# StartingPoint.net
KiCad netlist of a schematic drawn in EAGLE
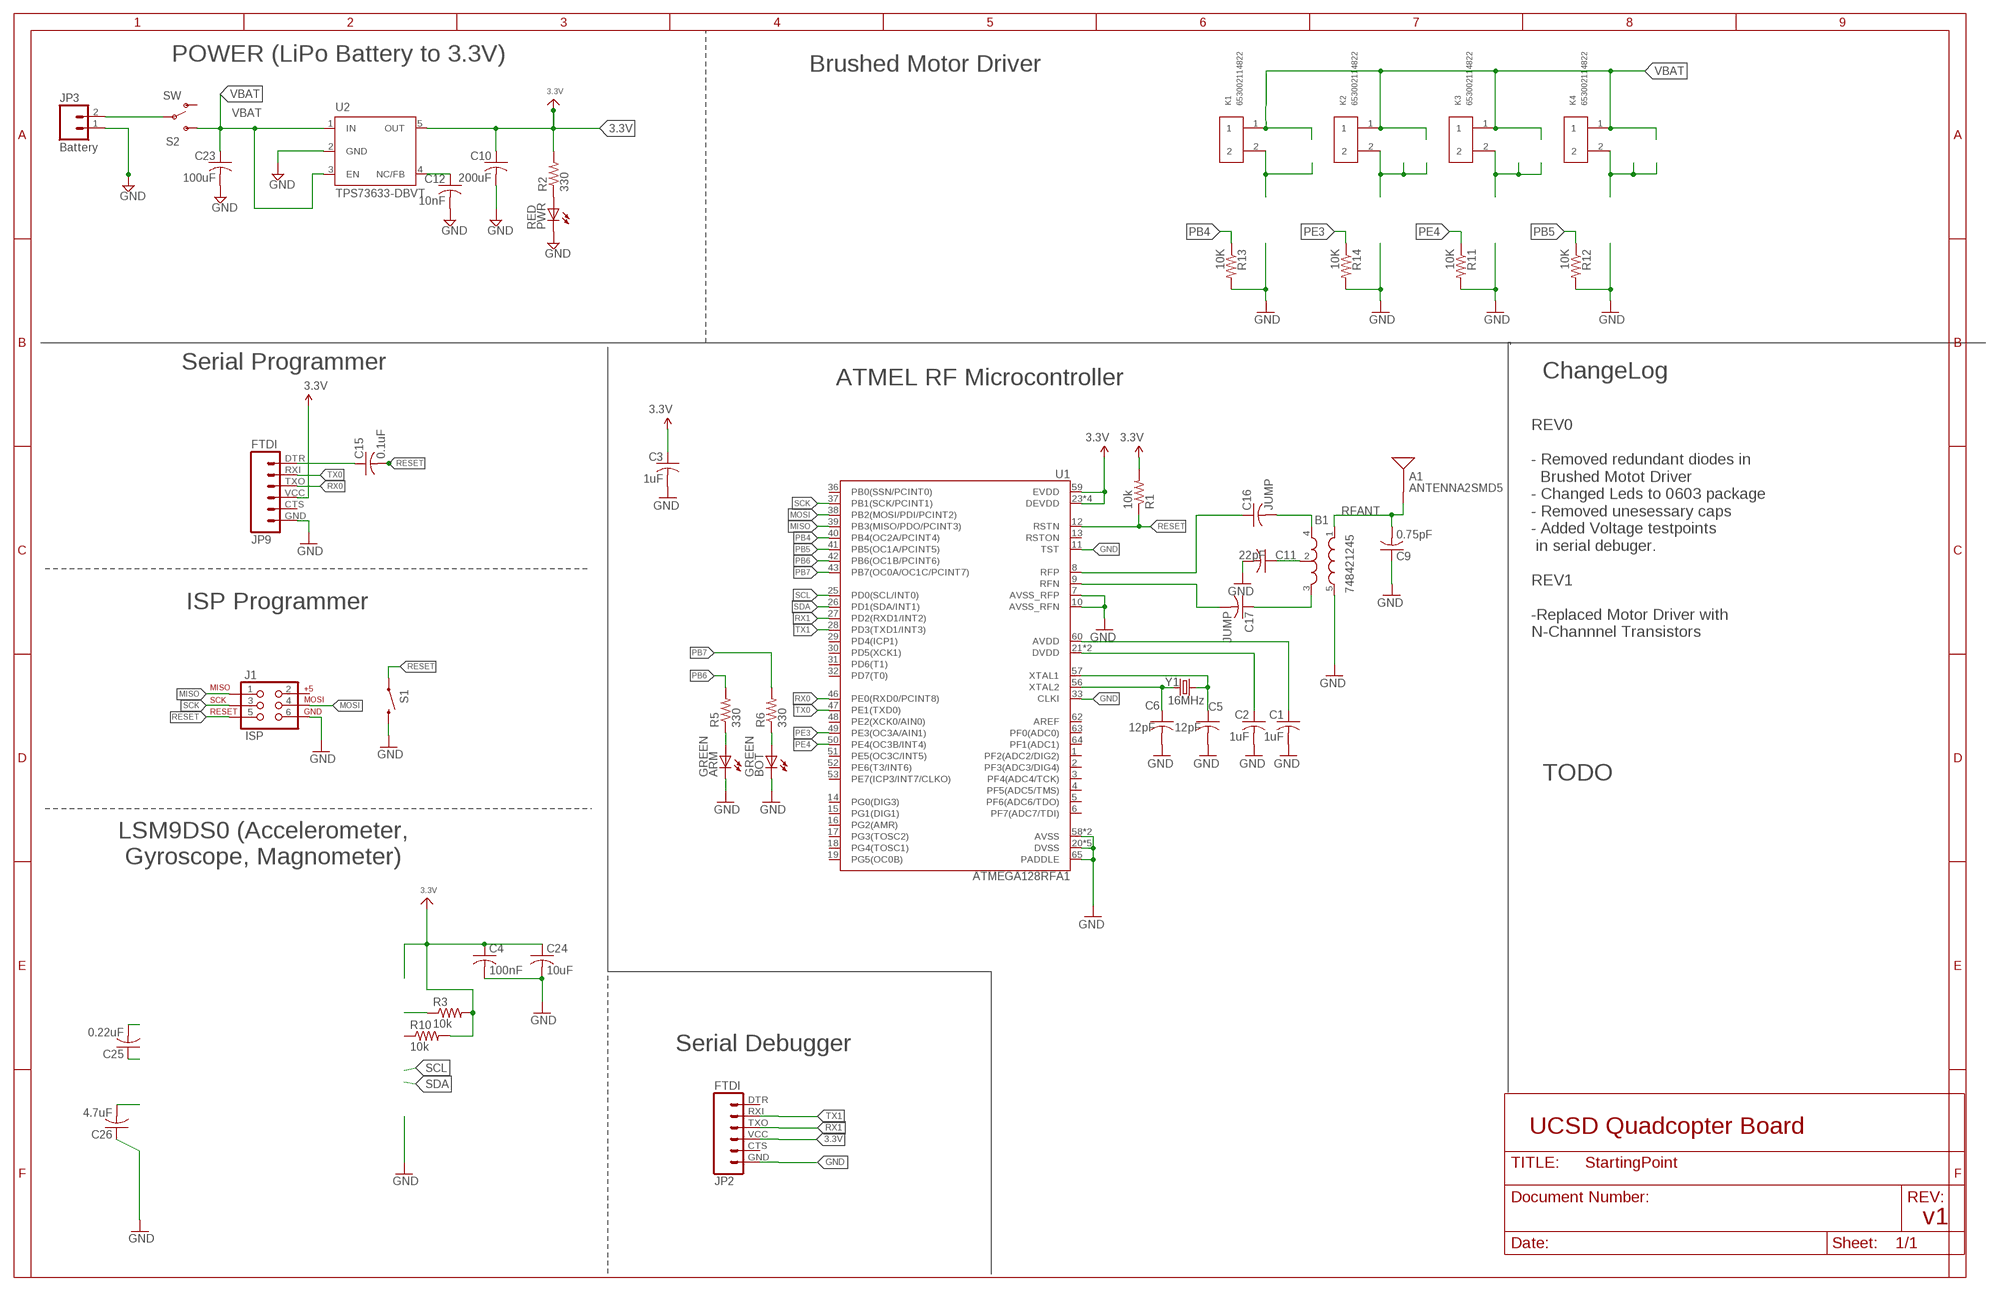
[diagram p0: schematic, sheet 1]

(export (version "E")
  (design (tool "Eeschema 10.0.6"))
  (components
    (comp (ref "A1")
      (value "ANTENNA2SMD5")
      (footprint "eagle-import:ANTENNA-CHIP5")
      (libsource (lib "eagle-import") (part "ANTENNA2SMD5"))
    )
    (comp (ref "ARM")
      (value "GREEN")
      (footprint "eagle-import:CHIP-LED0805")
      (libsource (lib "eagle-import") (part "LEDCHIP-LED0805"))
    )
    (comp (ref "B1")
      (value "748421245")
      (footprint "eagle-import:BALUN")
      (libsource (lib "eagle-import") (part "BALUN0805"))
    )
    (comp (ref "BOT")
      (value "GREEN")
      (footprint "eagle-import:CHIP-LED0805")
      (libsource (lib "eagle-import") (part "LEDCHIP-LED0805"))
    )
    (comp (ref "C1")
      (value "1uF")
      (footprint "eagle-import:C0805")
      (libsource (lib "eagle-import") (part "resistor_C-USC0805"))
    )
    (comp (ref "C2")
      (value "1uF")
      (footprint "eagle-import:C0805")
      (libsource (lib "eagle-import") (part "resistor_C-USC0805"))
    )
    (comp (ref "C3")
      (value "1uF")
      (footprint "eagle-import:C0805")
      (libsource (lib "eagle-import") (part "resistor_C-USC0805"))
    )
    (comp (ref "C4")
      (value "100nF")
      (footprint "eagle-import:C0805")
      (libsource (lib "eagle-import") (part "C-USC0805"))
    )
    (comp (ref "C5")
      (value "12pF")
      (footprint "eagle-import:C0805")
      (libsource (lib "eagle-import") (part "resistor_C-USC0805"))
    )
    (comp (ref "C6")
      (value "12pF")
      (footprint "eagle-import:C0805")
      (libsource (lib "eagle-import") (part "resistor_C-USC0805"))
    )
    (comp (ref "C9")
      (value "0.75pF")
      (footprint "eagle-import:C0805")
      (libsource (lib "eagle-import") (part "resistor_C-USC0805"))
    )
    (comp (ref "C10")
      (value "200uF")
      (footprint "eagle-import:C0805")
      (libsource (lib "eagle-import") (part "resistor_C-USC0805"))
    )
    (comp (ref "C11")
      (value "22pF")
      (footprint "eagle-import:C0805")
      (libsource (lib "eagle-import") (part "resistor_C-USC0805"))
    )
    (comp (ref "C12")
      (value "10nF")
      (footprint "eagle-import:C0805")
      (libsource (lib "eagle-import") (part "resistor_C-USC0805"))
    )
    (comp (ref "C15")
      (value "0.1uF")
      (footprint "eagle-import:C0805")
      (libsource (lib "eagle-import") (part "resistor_C-USC0805"))
    )
    (comp (ref "C16")
      (value "JUMP")
      (footprint "eagle-import:C0805")
      (libsource (lib "eagle-import") (part "resistor_C-USC0805"))
    )
    (comp (ref "C17")
      (value "JUMP")
      (footprint "eagle-import:C0805")
      (libsource (lib "eagle-import") (part "resistor_C-USC0805"))
    )
    (comp (ref "C23")
      (value "100uF")
      (footprint "eagle-import:C0805")
      (libsource (lib "eagle-import") (part "resistor_C-USC0805"))
    )
    (comp (ref "C24")
      (value "10uF")
      (footprint "eagle-import:C0805")
      (libsource (lib "eagle-import") (part "C-USC0805"))
    )
    (comp (ref "C25")
      (value "0.22uF")
      (footprint "eagle-import:C0805")
      (libsource (lib "eagle-import") (part "C-USC0805"))
    )
    (comp (ref "C26")
      (value "4.7uF")
      (footprint "eagle-import:C0805")
      (libsource (lib "eagle-import") (part "C-USC0805"))
    )
    (comp (ref "J1")
      (value "ISP")
      (footprint "eagle-import:2X3-NS")
      (libsource (lib "eagle-import") (part "AVR_SPI_PRG_6NS"))
    )
    (comp (ref "JP2")
      (value "FTDI")
      (footprint "eagle-import:FTDI_BASIC")
      (libsource (lib "eagle-import") (part "FTDI_BASICPTH"))
    )
    (comp (ref "JP3")
      (value "Battery")
      (footprint "eagle-import:1X02")
      (libsource (lib "eagle-import") (part "M02PTH"))
    )
    (comp (ref "JP9")
      (value "FTDI")
      (footprint "eagle-import:FTDI_BASIC")
      (libsource (lib "eagle-import") (part "FTDI_BASICPTH"))
    )
    (comp (ref "K1")
      (value "653002114822")
      (footprint "eagle-import:653002114822")
      (libsource (lib "eagle-import") (part "653002114822"))
    )
    (comp (ref "K2")
      (value "653002114822")
      (footprint "eagle-import:653002114822")
      (libsource (lib "eagle-import") (part "653002114822"))
    )
    (comp (ref "K3")
      (value "653002114822")
      (footprint "eagle-import:653002114822")
      (libsource (lib "eagle-import") (part "653002114822"))
    )
    (comp (ref "K4")
      (value "653002114822")
      (footprint "eagle-import:653002114822")
      (libsource (lib "eagle-import") (part "653002114822"))
    )
    (comp (ref "PWR")
      (value "RED")
      (footprint "eagle-import:CHIP-LED0805")
      (libsource (lib "eagle-import") (part "LEDCHIP-LED0805"))
    )
    (comp (ref "R1")
      (value "10k")
      (footprint "eagle-import:R0805")
      (libsource (lib "eagle-import") (part "R-US_R0805"))
    )
    (comp (ref "R2")
      (value "330")
      (footprint "eagle-import:R0805")
      (libsource (lib "eagle-import") (part "R-US_R0805"))
    )
    (comp (ref "R3")
      (value "10k")
      (footprint "eagle-import:R0805")
      (libsource (lib "eagle-import") (part "R-US_R0805"))
    )
    (comp (ref "R5")
      (value "330")
      (footprint "eagle-import:R0805")
      (libsource (lib "eagle-import") (part "R-US_R0805"))
    )
    (comp (ref "R6")
      (value "330")
      (footprint "eagle-import:R0805")
      (libsource (lib "eagle-import") (part "R-US_R0805"))
    )
    (comp (ref "R10")
      (value "10k")
      (footprint "eagle-import:R0805")
      (libsource (lib "eagle-import") (part "R-US_R0805"))
    )
    (comp (ref "R11")
      (value "10K")
      (footprint "eagle-import:R0805")
      (libsource (lib "eagle-import") (part "R-US_R0805"))
    )
    (comp (ref "R12")
      (value "10K")
      (footprint "eagle-import:R0805")
      (libsource (lib "eagle-import") (part "R-US_R0805"))
    )
    (comp (ref "R13")
      (value "10K")
      (footprint "eagle-import:R0805")
      (libsource (lib "eagle-import") (part "R-US_R0805"))
    )
    (comp (ref "R14")
      (value "10K")
      (footprint "eagle-import:R0805")
      (libsource (lib "eagle-import") (part "R-US_R0805"))
    )
    (comp (ref "S1")
      (value "SWITCH-MOMENTARY-2SMD")
      (footprint "eagle-import:TACTILE_SWITCH_SMD")
      (libsource (lib "eagle-import") (part "SWITCH-MOMENTARY-2SMD"))
    )
    (comp (ref "S2")
      (value "SW")
      (footprint "eagle-import:SWITCH-SPDT")
      (libsource (lib "eagle-import") (part "SWITCH-SPDTPTH"))
    )
    (comp (ref "U1")
      (value "ATMEGA128RFA1")
      (footprint "eagle-import:QFN-64")
      (libsource (lib "eagle-import") (part "ATMEGA128RFA1"))
    )
    (comp (ref "U2")
      (value "TPS73633-DBVT")
      (footprint "eagle-import:SOT23-DBV")
      (libsource (lib "eagle-import") (part "TPS73633-DBVT"))
    )
    (comp (ref "Y1")
      (value "16MHz")
      (footprint "eagle-import:CRYSTAL-SMD-5X3")
      (libsource (lib "eagle-import") (part "CRYSTAL5X3"))
    )
  )
  (nets
    (net (code "1") (name "/RFANT") (class "Default")
      (node (ref "A1") (pin "FEED") (pinfunction "SIGNAL_FEED") (pintype "bidirectional"))
      (node (ref "B1") (pin "1") (pinfunction "IN_1") (pintype "bidirectional"))
      (node (ref "C9") (pin "2") (pinfunction "2_2") (pintype "passive"))
    )
    (net (code "2") (name "3.3V") (class "Default")
      (node (ref "C10") (pin "1") (pinfunction "1_1") (pintype "passive"))
      (node (ref "C24") (pin "1") (pinfunction "1_1") (pintype "passive"))
      (node (ref "C3") (pin "1") (pinfunction "1_1") (pintype "passive"))
      (node (ref "C4") (pin "1") (pinfunction "1_1") (pintype "passive"))
      (node (ref "JP2") (pin "VCC") (pinfunction "4_VCC") (pintype "passive"))
      (node (ref "JP9") (pin "VCC") (pinfunction "4_VCC") (pintype "passive"))
      (node (ref "R1") (pin "2") (pinfunction "2_2") (pintype "passive"))
      (node (ref "R10") (pin "2") (pinfunction "2_2") (pintype "passive"))
      (node (ref "R2") (pin "2") (pinfunction "2_2") (pintype "passive"))
      (node (ref "R3") (pin "2") (pinfunction "2_2") (pintype "passive"))
      (node (ref "U1") (pin "23") (pinfunction "DEVDD_23") (pintype "bidirectional"))
      (node (ref "U1") (pin "34") (pinfunction "DEVDD_34") (pintype "bidirectional"))
      (node (ref "U1") (pin "44") (pinfunction "DEVDD_44") (pintype "bidirectional"))
      (node (ref "U1") (pin "54") (pinfunction "DEVDD_54") (pintype "bidirectional"))
      (node (ref "U1") (pin "59") (pinfunction "EVDD_59") (pintype "bidirectional"))
      (node (ref "U2") (pin "5") (pinfunction "OUT_5") (pintype "passive"))
    )
    (net (code "3") (name "GND") (class "Default")
      (node (ref "ARM") (pin "C") (pinfunction "C_C") (pintype "passive"))
      (node (ref "B1") (pin "5") (pinfunction "GND_5") (pintype "bidirectional"))
      (node (ref "BOT") (pin "C") (pinfunction "C_C") (pintype "passive"))
      (node (ref "C1") (pin "2") (pinfunction "2_2") (pintype "passive"))
      (node (ref "C10") (pin "2") (pinfunction "2_2") (pintype "passive"))
      (node (ref "C11") (pin "2") (pinfunction "2_2") (pintype "passive"))
      (node (ref "C12") (pin "2") (pinfunction "2_2") (pintype "passive"))
      (node (ref "C2") (pin "2") (pinfunction "2_2") (pintype "passive"))
      (node (ref "C23") (pin "2") (pinfunction "2_2") (pintype "passive"))
      (node (ref "C24") (pin "2") (pinfunction "2_2") (pintype "passive"))
      (node (ref "C26") (pin "1") (pinfunction "1_1") (pintype "passive"))
      (node (ref "C3") (pin "2") (pinfunction "2_2") (pintype "passive"))
      (node (ref "C4") (pin "2") (pinfunction "2_2") (pintype "passive"))
      (node (ref "C5") (pin "2") (pinfunction "2_2") (pintype "passive"))
      (node (ref "C6") (pin "2") (pinfunction "2_2") (pintype "passive"))
      (node (ref "C9") (pin "1") (pinfunction "1_1") (pintype "passive"))
      (node (ref "J1") (pin "6") (pinfunction "6_6") (pintype "passive"))
      (node (ref "JP2") (pin "GND") (pinfunction "6_GND") (pintype "passive"))
      (node (ref "JP3") (pin "1") (pinfunction "1_1") (pintype "passive"))
      (node (ref "JP9") (pin "GND") (pinfunction "6_GND") (pintype "passive"))
      (node (ref "PWR") (pin "C") (pinfunction "C_C") (pintype "passive"))
      (node (ref "R11") (pin "2") (pinfunction "2_2") (pintype "passive"))
      (node (ref "R12") (pin "2") (pinfunction "2_2") (pintype "passive"))
      (node (ref "R13") (pin "2") (pinfunction "2_2") (pintype "passive"))
      (node (ref "R14") (pin "2") (pinfunction "2_2") (pintype "passive"))
      (node (ref "S1") (pin "3") (pinfunction "2_3") (pintype "passive"))
      (node (ref "U1") (pin "10") (pinfunction "AVSS_RFN_10") (pintype "bidirectional"))
      (node (ref "U1") (pin "11") (pinfunction "TST_11") (pintype "bidirectional"))
      (node (ref "U1") (pin "20") (pinfunction "DVSS_20") (pintype "bidirectional"))
      (node (ref "U1") (pin "24") (pinfunction "DVSS_24") (pintype "bidirectional"))
      (node (ref "U1") (pin "33") (pinfunction "CLKI_33") (pintype "bidirectional"))
      (node (ref "U1") (pin "35") (pinfunction "DVSS_35") (pintype "bidirectional"))
      (node (ref "U1") (pin "45") (pinfunction "DVSS_45") (pintype "bidirectional"))
      (node (ref "U1") (pin "55") (pinfunction "DVSS_55") (pintype "bidirectional"))
      (node (ref "U1") (pin "58") (pinfunction "AVSS_58") (pintype "bidirectional"))
      (node (ref "U1") (pin "61") (pinfunction "AVSS_61") (pintype "bidirectional"))
      (node (ref "U1") (pin "65") (pinfunction "PADDLE_65") (pintype "bidirectional"))
      (node (ref "U1") (pin "7") (pinfunction "AVSS_RFP_7") (pintype "bidirectional"))
      (node (ref "U2") (pin "2") (pinfunction "GND_2") (pintype "input"))
    )
    (net (code "4") (name "MISO") (class "Default")
      (node (ref "J1") (pin "1") (pinfunction "1_1") (pintype "passive"))
      (node (ref "U1") (pin "39") (pinfunction "PB3(MISO/PDO/PCINT3)_39") (pintype "bidirectional"))
    )
    (net (code "5") (name "MOSI") (class "Default")
      (node (ref "J1") (pin "4") (pinfunction "4_4") (pintype "passive"))
      (node (ref "U1") (pin "38") (pinfunction "PB2(MOSI/PDI/PCINT2)_38") (pintype "bidirectional"))
    )
    (net (code "6") (name "Net-(ARM-PadA)") (class "Default")
      (node (ref "ARM") (pin "A") (pinfunction "A_A") (pintype "passive"))
      (node (ref "R5") (pin "1") (pinfunction "1_1") (pintype "passive"))
    )
    (net (code "7") (name "Net-(B1-GND-Pad2)") (class "Default")
      (node (ref "B1") (pin "2") (pinfunction "GND_2") (pintype "bidirectional"))
      (node (ref "C11") (pin "1") (pinfunction "1_1") (pintype "passive"))
    )
    (net (code "8") (name "Net-(B1-OUT1)") (class "Default")
      (node (ref "B1") (pin "4") (pinfunction "OUT1_4") (pintype "bidirectional"))
      (node (ref "C16") (pin "2") (pinfunction "2_2") (pintype "passive"))
    )
    (net (code "9") (name "Net-(B1-OUT2)") (class "Default")
      (node (ref "B1") (pin "3") (pinfunction "OUT2_3") (pintype "bidirectional"))
      (node (ref "C17") (pin "1") (pinfunction "1_1") (pintype "passive"))
    )
    (net (code "10") (name "Net-(BOT-PadA)") (class "Default")
      (node (ref "BOT") (pin "A") (pinfunction "A_A") (pintype "passive"))
      (node (ref "R6") (pin "1") (pinfunction "1_1") (pintype "passive"))
    )
    (net (code "11") (name "Net-(C2-Pad1)") (class "Default")
      (node (ref "C2") (pin "1") (pinfunction "1_1") (pintype "passive"))
      (node (ref "U1") (pin "21") (pinfunction "DVDD_21") (pintype "bidirectional"))
      (node (ref "U1") (pin "22") (pinfunction "DVDD_22") (pintype "bidirectional"))
    )
    (net (code "12") (name "Net-(JP9-1)") (class "Default")
      (node (ref "C15") (pin "1") (pinfunction "1_1") (pintype "passive"))
      (node (ref "JP9") (pin "DTR") (pinfunction "1_DTR") (pintype "passive"))
    )
    (net (code "13") (name "Net-(PWR-PadA)") (class "Default")
      (node (ref "PWR") (pin "A") (pinfunction "A_A") (pintype "passive"))
      (node (ref "R2") (pin "1") (pinfunction "1_1") (pintype "passive"))
    )
    (net (code "14") (name "Net-(S2-P)") (class "Default")
      (node (ref "JP3") (pin "2") (pinfunction "2_2") (pintype "passive"))
      (node (ref "S2") (pin "2") (pinfunction "P_2") (pintype "passive"))
    )
    (net (code "15") (name "Net-(U1-AVDD)") (class "Default")
      (node (ref "C1") (pin "1") (pinfunction "1_1") (pintype "passive"))
      (node (ref "U1") (pin "60") (pinfunction "AVDD_60") (pintype "bidirectional"))
    )
    (net (code "16") (name "Net-(U1-RFN)") (class "Default")
      (node (ref "C17") (pin "2") (pinfunction "2_2") (pintype "passive"))
      (node (ref "U1") (pin "9") (pinfunction "RFN_9") (pintype "bidirectional"))
    )
    (net (code "17") (name "Net-(U1-RFP)") (class "Default")
      (node (ref "C16") (pin "1") (pinfunction "1_1") (pintype "passive"))
      (node (ref "U1") (pin "8") (pinfunction "RFP_8") (pintype "bidirectional"))
    )
    (net (code "18") (name "Net-(U1-XTAL1)") (class "Default")
      (node (ref "C5") (pin "1") (pinfunction "1_1") (pintype "passive"))
      (node (ref "U1") (pin "57") (pinfunction "XTAL1_57") (pintype "bidirectional"))
      (node (ref "Y1") (pin "3") (pinfunction "2_3") (pintype "passive"))
    )
    (net (code "19") (name "Net-(U1-XTAL2)") (class "Default")
      (node (ref "C6") (pin "1") (pinfunction "1_1") (pintype "passive"))
      (node (ref "U1") (pin "56") (pinfunction "XTAL2_56") (pintype "bidirectional"))
      (node (ref "Y1") (pin "1") (pinfunction "1_1") (pintype "passive"))
    )
    (net (code "20") (name "Net-(U2-NC{slash}FB)") (class "Default")
      (node (ref "C12") (pin "1") (pinfunction "1_1") (pintype "passive"))
      (node (ref "U2") (pin "4") (pinfunction "NC/FB_4") (pintype "passive"))
    )
    (net (code "21") (name "PB4") (class "Default")
      (node (ref "R13") (pin "1") (pinfunction "1_1") (pintype "passive"))
      (node (ref "U1") (pin "40") (pinfunction "PB4(OC2A/PCINT4)_40") (pintype "bidirectional"))
    )
    (net (code "22") (name "PB5") (class "Default")
      (node (ref "R12") (pin "1") (pinfunction "1_1") (pintype "passive"))
      (node (ref "U1") (pin "41") (pinfunction "PB5(OC1A/PCINT5)_41") (pintype "bidirectional"))
    )
    (net (code "23") (name "PB6") (class "Default")
      (node (ref "R5") (pin "2") (pinfunction "2_2") (pintype "passive"))
      (node (ref "U1") (pin "42") (pinfunction "PB6(OC1B/PCINT6)_42") (pintype "bidirectional"))
    )
    (net (code "24") (name "PB7") (class "Default")
      (node (ref "R6") (pin "2") (pinfunction "2_2") (pintype "passive"))
      (node (ref "U1") (pin "43") (pinfunction "PB7(OC0A/OC1C/PCINT7)_43") (pintype "bidirectional"))
    )
    (net (code "25") (name "PE3") (class "Default")
      (node (ref "R14") (pin "1") (pinfunction "1_1") (pintype "passive"))
      (node (ref "U1") (pin "49") (pinfunction "PE3(OC3A/AIN1)_49") (pintype "bidirectional"))
    )
    (net (code "26") (name "PE4") (class "Default")
      (node (ref "R11") (pin "1") (pinfunction "1_1") (pintype "passive"))
      (node (ref "U1") (pin "50") (pinfunction "PE4(OC3B/INT4)_50") (pintype "bidirectional"))
    )
    (net (code "27") (name "RESET") (class "Default")
      (node (ref "C15") (pin "2") (pinfunction "2_2") (pintype "passive"))
      (node (ref "J1") (pin "5") (pinfunction "5_5") (pintype "passive"))
      (node (ref "R1") (pin "1") (pinfunction "1_1") (pintype "passive"))
      (node (ref "S1") (pin "1") (pinfunction "1_1") (pintype "passive"))
      (node (ref "U1") (pin "12") (pinfunction "RSTN_12") (pintype "bidirectional"))
    )
    (net (code "28") (name "RX0") (class "Default")
      (node (ref "JP9") (pin "TXO") (pinfunction "3_TXO") (pintype "passive"))
      (node (ref "U1") (pin "46") (pinfunction "PE0(RXD0/PCINT8)_46") (pintype "bidirectional"))
    )
    (net (code "29") (name "RX1") (class "Default")
      (node (ref "JP2") (pin "TXO") (pinfunction "3_TXO") (pintype "passive"))
      (node (ref "U1") (pin "27") (pinfunction "PD2(RXD1/INT2)_27") (pintype "bidirectional"))
    )
    (net (code "30") (name "SCK") (class "Default")
      (node (ref "J1") (pin "3") (pinfunction "3_3") (pintype "passive"))
      (node (ref "U1") (pin "37") (pinfunction "PB1(SCK/PCINT1)_37") (pintype "bidirectional"))
    )
    (net (code "31") (name "SCL") (class "Default")
      (node (ref "U1") (pin "25") (pinfunction "PD0(SCL/INT0)_25") (pintype "bidirectional"))
    )
    (net (code "32") (name "SDA") (class "Default")
      (node (ref "U1") (pin "26") (pinfunction "PD1(SDA/INT1)_26") (pintype "bidirectional"))
    )
    (net (code "33") (name "TX0") (class "Default")
      (node (ref "JP9") (pin "RXI") (pinfunction "2_RXI") (pintype "passive"))
      (node (ref "U1") (pin "47") (pinfunction "PE1(TXD0)_47") (pintype "bidirectional"))
    )
    (net (code "34") (name "TX1") (class "Default")
      (node (ref "JP2") (pin "RXI") (pinfunction "2_RXI") (pintype "passive"))
      (node (ref "U1") (pin "28") (pinfunction "PD3(TXD1/INT3)_28") (pintype "bidirectional"))
    )
    (net (code "35") (name "VBAT") (class "Default")
      (node (ref "C23") (pin "1") (pinfunction "1_1") (pintype "passive"))
      (node (ref "K1") (pin "1") (pinfunction "1_1") (pintype "bidirectional"))
      (node (ref "K2") (pin "1") (pinfunction "1_1") (pintype "bidirectional"))
      (node (ref "K3") (pin "1") (pinfunction "1_1") (pintype "bidirectional"))
      (node (ref "K4") (pin "1") (pinfunction "1_1") (pintype "bidirectional"))
      (node (ref "S2") (pin "3") (pinfunction "S_3") (pintype "passive"))
      (node (ref "U2") (pin "1") (pinfunction "IN_1") (pintype "input"))
      (node (ref "U2") (pin "3") (pinfunction "EN_3") (pintype "power_in"))
    )
    (net (code "36") (name "unconnected-(C25-Pad1)") (class "Default")
      (node (ref "C25") (pin "1") (pinfunction "1_1") (pintype "passive"))
    )
    (net (code "37") (name "unconnected-(C25-Pad2)") (class "Default")
      (node (ref "C25") (pin "2") (pinfunction "2_2") (pintype "passive"))
    )
    (net (code "38") (name "unconnected-(C26-Pad2)") (class "Default")
      (node (ref "C26") (pin "2") (pinfunction "2_2") (pintype "passive"))
    )
    (net (code "39") (name "unconnected-(J1-Pad2)") (class "Default")
      (node (ref "J1") (pin "2") (pinfunction "2_2") (pintype "passive"))
    )
    (net (code "40") (name "unconnected-(JP2-1-PadDTR)") (class "Default")
      (node (ref "JP2") (pin "DTR") (pinfunction "1_DTR") (pintype "passive"))
    )
    (net (code "41") (name "unconnected-(JP2-5-PadCTS)") (class "Default")
      (node (ref "JP2") (pin "CTS") (pinfunction "5_CTS") (pintype "passive"))
    )
    (net (code "42") (name "unconnected-(JP9-5-PadCTS)") (class "Default")
      (node (ref "JP9") (pin "CTS") (pinfunction "5_CTS") (pintype "passive"))
    )
    (net (code "43") (name "unconnected-(K1-Pad2)") (class "Default")
      (node (ref "K1") (pin "2") (pinfunction "2_2") (pintype "bidirectional"))
    )
    (net (code "44") (name "unconnected-(K2-Pad2)") (class "Default")
      (node (ref "K2") (pin "2") (pinfunction "2_2") (pintype "bidirectional"))
    )
    (net (code "45") (name "unconnected-(K3-Pad2)") (class "Default")
      (node (ref "K3") (pin "2") (pinfunction "2_2") (pintype "bidirectional"))
    )
    (net (code "46") (name "unconnected-(K4-Pad2)") (class "Default")
      (node (ref "K4") (pin "2") (pinfunction "2_2") (pintype "bidirectional"))
    )
    (net (code "47") (name "unconnected-(R3-Pad1)") (class "Default")
      (node (ref "R3") (pin "1") (pinfunction "1_1") (pintype "passive"))
    )
    (net (code "48") (name "unconnected-(R10-Pad1)") (class "Default")
      (node (ref "R10") (pin "1") (pinfunction "1_1") (pintype "passive"))
    )
    (net (code "49") (name "unconnected-(S2-O-Pad1)") (class "Default")
      (node (ref "S2") (pin "1") (pinfunction "O_1") (pintype "passive"))
    )
    (net (code "50") (name "unconnected-(U1-AREF-Pad62)") (class "Default")
      (node (ref "U1") (pin "62") (pinfunction "AREF_62") (pintype "bidirectional"))
    )
    (net (code "51") (name "unconnected-(U1-PB0(SSN{slash}PCINT0)-Pad36)") (class "Default")
      (node (ref "U1") (pin "36") (pinfunction "PB0(SSN/PCINT0)_36") (pintype "bidirectional"))
    )
    (net (code "52") (name "unconnected-(U1-PD4(ICP1)-Pad29)") (class "Default")
      (node (ref "U1") (pin "29") (pinfunction "PD4(ICP1)_29") (pintype "bidirectional"))
    )
    (net (code "53") (name "unconnected-(U1-PD5(XCK1)-Pad30)") (class "Default")
      (node (ref "U1") (pin "30") (pinfunction "PD5(XCK1)_30") (pintype "bidirectional"))
    )
    (net (code "54") (name "unconnected-(U1-PD6(T1)-Pad31)") (class "Default")
      (node (ref "U1") (pin "31") (pinfunction "PD6(T1)_31") (pintype "bidirectional"))
    )
    (net (code "55") (name "unconnected-(U1-PD7(T0)-Pad32)") (class "Default")
      (node (ref "U1") (pin "32") (pinfunction "PD7(T0)_32") (pintype "bidirectional"))
    )
    (net (code "56") (name "unconnected-(U1-PE2(XCK0{slash}AIN0)-Pad48)") (class "Default")
      (node (ref "U1") (pin "48") (pinfunction "PE2(XCK0/AIN0)_48") (pintype "bidirectional"))
    )
    (net (code "57") (name "unconnected-(U1-PE5(OC3C{slash}INT5)-Pad51)") (class "Default")
      (node (ref "U1") (pin "51") (pinfunction "PE5(OC3C/INT5)_51") (pintype "bidirectional"))
    )
    (net (code "58") (name "unconnected-(U1-PE6(T3{slash}INT6)-Pad52)") (class "Default")
      (node (ref "U1") (pin "52") (pinfunction "PE6(T3/INT6)_52") (pintype "bidirectional"))
    )
    (net (code "59") (name "unconnected-(U1-PE7(ICP3{slash}INT7{slash}CLKO)-Pad53)") (class "Default")
      (node (ref "U1") (pin "53") (pinfunction "PE7(ICP3/INT7/CLKO)_53") (pintype "bidirectional"))
    )
    (net (code "60") (name "unconnected-(U1-PF0(ADC0)-Pad63)") (class "Default")
      (node (ref "U1") (pin "63") (pinfunction "PF0(ADC0)_63") (pintype "bidirectional"))
    )
    (net (code "61") (name "unconnected-(U1-PF1(ADC1)-Pad64)") (class "Default")
      (node (ref "U1") (pin "64") (pinfunction "PF1(ADC1)_64") (pintype "bidirectional"))
    )
    (net (code "62") (name "unconnected-(U1-PF2(ADC2{slash}DIG2)-Pad1)") (class "Default")
      (node (ref "U1") (pin "1") (pinfunction "PF2(ADC2/DIG2)_1") (pintype "bidirectional"))
    )
    (net (code "63") (name "unconnected-(U1-PF3(ADC3{slash}DIG4)-Pad2)") (class "Default")
      (node (ref "U1") (pin "2") (pinfunction "PF3(ADC3/DIG4)_2") (pintype "bidirectional"))
    )
    (net (code "64") (name "unconnected-(U1-PF4(ADC4{slash}TCK)-Pad3)") (class "Default")
      (node (ref "U1") (pin "3") (pinfunction "PF4(ADC4/TCK)_3") (pintype "bidirectional"))
    )
    (net (code "65") (name "unconnected-(U1-PF5(ADC5{slash}TMS)-Pad4)") (class "Default")
      (node (ref "U1") (pin "4") (pinfunction "PF5(ADC5/TMS)_4") (pintype "bidirectional"))
    )
    (net (code "66") (name "unconnected-(U1-PF6(ADC6{slash}TDO)-Pad5)") (class "Default")
      (node (ref "U1") (pin "5") (pinfunction "PF6(ADC6/TDO)_5") (pintype "bidirectional"))
    )
    (net (code "67") (name "unconnected-(U1-PF7(ADC7{slash}TDI)-Pad6)") (class "Default")
      (node (ref "U1") (pin "6") (pinfunction "PF7(ADC7/TDI)_6") (pintype "bidirectional"))
    )
    (net (code "68") (name "unconnected-(U1-PG0(DIG3)-Pad14)") (class "Default")
      (node (ref "U1") (pin "14") (pinfunction "PG0(DIG3)_14") (pintype "bidirectional"))
    )
    (net (code "69") (name "unconnected-(U1-PG1(DIG1)-Pad15)") (class "Default")
      (node (ref "U1") (pin "15") (pinfunction "PG1(DIG1)_15") (pintype "bidirectional"))
    )
    (net (code "70") (name "unconnected-(U1-PG2(AMR)-Pad16)") (class "Default")
      (node (ref "U1") (pin "16") (pinfunction "PG2(AMR)_16") (pintype "bidirectional"))
    )
    (net (code "71") (name "unconnected-(U1-PG3(TOSC2)-Pad17)") (class "Default")
      (node (ref "U1") (pin "17") (pinfunction "PG3(TOSC2)_17") (pintype "bidirectional"))
    )
    (net (code "72") (name "unconnected-(U1-PG4(TOSC1)-Pad18)") (class "Default")
      (node (ref "U1") (pin "18") (pinfunction "PG4(TOSC1)_18") (pintype "bidirectional"))
    )
    (net (code "73") (name "unconnected-(U1-PG5(OC0B)-Pad19)") (class "Default")
      (node (ref "U1") (pin "19") (pinfunction "PG5(OC0B)_19") (pintype "bidirectional"))
    )
    (net (code "74") (name "unconnected-(U1-RSTON-Pad13)") (class "Default")
      (node (ref "U1") (pin "13") (pinfunction "RSTON_13") (pintype "bidirectional"))
    )
  )
)
